# xcvr.net
KiCad netlist of a schematic drawn in Altium Designer
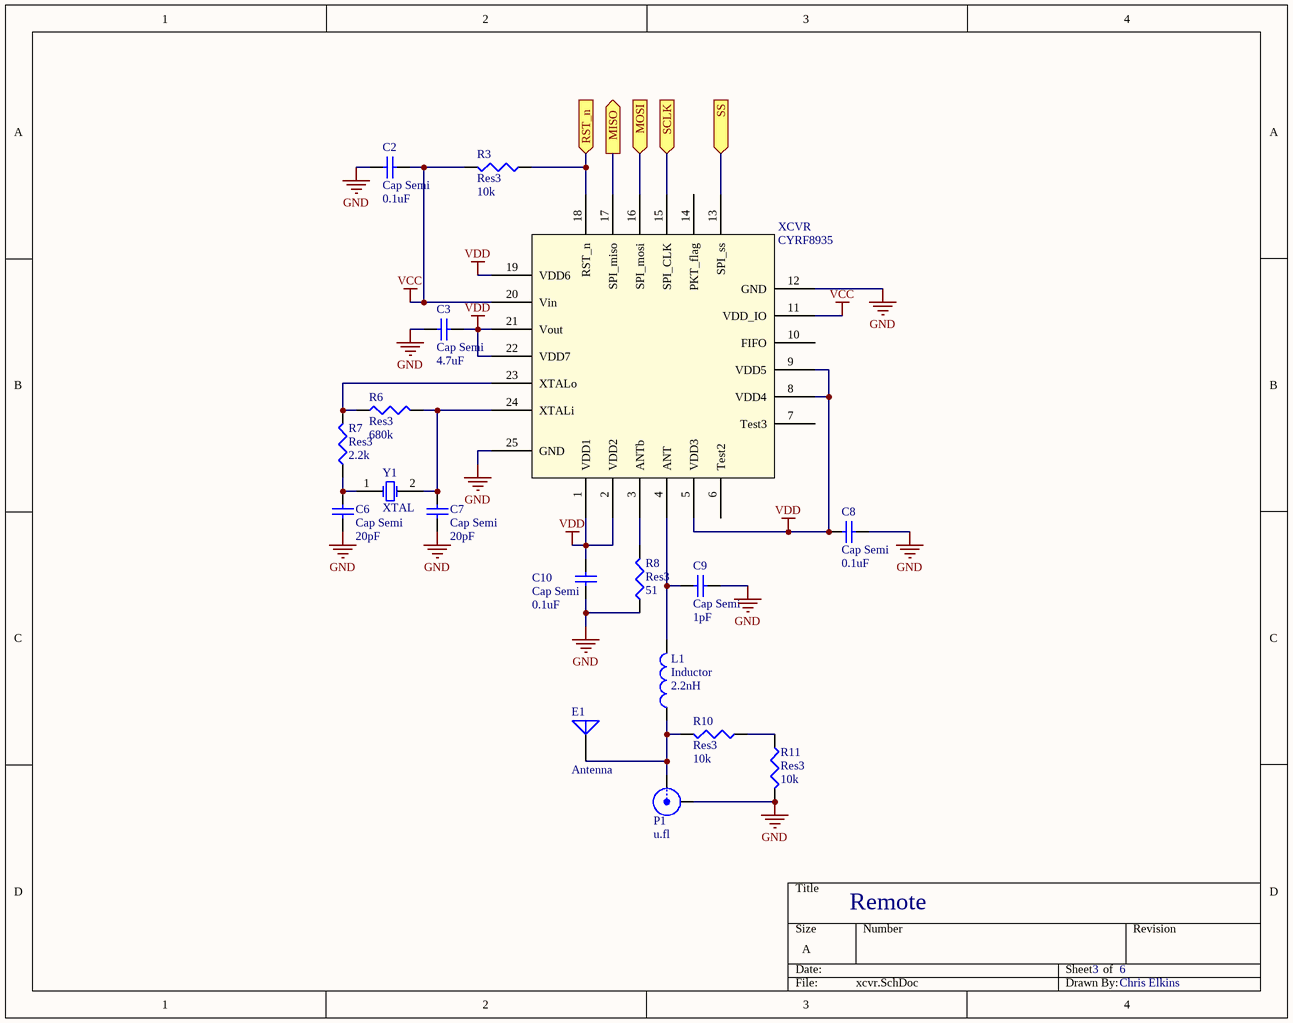
[diagram p0: xcvr.SchDoc]

(export (version "E")
  (design (tool "Eeschema 10.0.6"))
  (components
    (comp (ref "C2")
      (value "Cap Semi")
      (footprint "CAPC1608L")
      (description "Capacitor (Semiconductor SIM Model)")
      (fields (field (name "ALTIUM_VALUE") "0.1uF") (field (name "PUBLISHER") "Altium Limited"))
      (libsource (lib "Miscellaneous Devices") (part "Cap Semi"))
    )
    (comp (ref "C3")
      (value "Cap Semi")
      (footprint "CAPC1608L")
      (description "Capacitor (Semiconductor SIM Model)")
      (fields (field (name "ALTIUM_VALUE") "4.7uF") (field (name "PUBLISHER") "Altium Limited"))
      (libsource (lib "Miscellaneous Devices") (part "Cap Semi"))
    )
    (comp (ref "C6")
      (value "Cap Semi")
      (footprint "CAPC1608L")
      (description "Capacitor (Semiconductor SIM Model)")
      (fields (field (name "ALTIUM_VALUE") "20pF") (field (name "PUBLISHER") "Altium Limited"))
      (libsource (lib "Miscellaneous Devices") (part "Cap Semi"))
    )
    (comp (ref "C7")
      (value "Cap Semi")
      (footprint "CAPC1608L")
      (description "Capacitor (Semiconductor SIM Model)")
      (fields (field (name "ALTIUM_VALUE") "20pF") (field (name "PUBLISHER") "Altium Limited"))
      (libsource (lib "Miscellaneous Devices") (part "Cap Semi"))
    )
    (comp (ref "C8")
      (value "Cap Semi")
      (footprint "CAPC1608L")
      (description "Capacitor (Semiconductor SIM Model)")
      (fields (field (name "ALTIUM_VALUE") "0.1uF") (field (name "PUBLISHER") "Altium Limited"))
      (libsource (lib "Miscellaneous Devices") (part "Cap Semi"))
    )
    (comp (ref "C9")
      (value "Cap Semi")
      (footprint "CAPC1608L")
      (description "Capacitor (Semiconductor SIM Model)")
      (fields (field (name "ALTIUM_VALUE") "1pF") (field (name "PUBLISHER") "Altium Limited"))
      (libsource (lib "Miscellaneous Devices") (part "Cap Semi"))
    )
    (comp (ref "C10")
      (value "Cap Semi")
      (footprint "CAPC1608L")
      (description "Capacitor (Semiconductor SIM Model)")
      (fields (field (name "ALTIUM_VALUE") "0.1uF") (field (name "PUBLISHER") "Altium Limited"))
      (libsource (lib "Miscellaneous Devices") (part "Cap Semi"))
    )
    (comp (ref "E1")
      (value "Antenna")
      (footprint "PIN1")
      (description "Generic Antenna")
      (fields (field (name "PUBLISHER") "Altium Limited"))
      (libsource (lib "Miscellaneous Devices") (part "Antenna"))
    )
    (comp (ref "L1")
      (value "Inductor")
      (footprint "INDC1608L")
      (fields (field (name "ALTIUM_VALUE") "2.2nH") (field (name "PUBLISHER") "Altium Limited"))
      (libsource (lib "Miscellaneous Devices") (part "Inductor"))
    )
    (comp (ref "P1")
      (value "u.fl")
      (footprint "U.FL connector")
      (description "BNC Elbow Connector")
      (fields (field (name "PUBLISHER") "Altium Limited"))
      (libsource (lib "Miscellaneous Connectors") (part "BNC"))
    )
    (comp (ref "R3")
      (value "Res3")
      (footprint "RESC1608L")
      (description "Resistor")
      (fields (field (name "ALTIUM_VALUE") "10k") (field (name "PUBLISHER") "Altium Limited"))
      (libsource (lib "Miscellaneous Devices") (part "Res3"))
    )
    (comp (ref "R6")
      (value "Res3")
      (footprint "RESC1608L")
      (description "Resistor")
      (fields (field (name "ALTIUM_VALUE") "680k") (field (name "PUBLISHER") "Altium Limited"))
      (libsource (lib "Miscellaneous Devices") (part "Res3"))
    )
    (comp (ref "R7")
      (value "Res3")
      (footprint "RESC1608L")
      (description "Resistor")
      (fields (field (name "ALTIUM_VALUE") "2.2k") (field (name "PUBLISHER") "Altium Limited"))
      (libsource (lib "Miscellaneous Devices") (part "Res3"))
    )
    (comp (ref "R8")
      (value "Res3")
      (footprint "RESC1608L")
      (description "Resistor")
      (fields (field (name "ALTIUM_VALUE") "51") (field (name "PUBLISHER") "Altium Limited"))
      (libsource (lib "Miscellaneous Devices") (part "Res3"))
    )
    (comp (ref "R10")
      (value "Res3")
      (footprint "RESC1608L")
      (description "Resistor")
      (fields (field (name "ALTIUM_VALUE") "10k") (field (name "PUBLISHER") "Altium Limited"))
      (libsource (lib "Miscellaneous Devices") (part "Res3"))
    )
    (comp (ref "R11")
      (value "Res3")
      (footprint "RESC1608L")
      (description "Resistor")
      (fields (field (name "ALTIUM_VALUE") "10k") (field (name "PUBLISHER") "Altium Limited"))
      (libsource (lib "Miscellaneous Devices") (part "Res3"))
    )
    (comp (ref "XCVR")
      (value "CYRF8935")
      (footprint "QFN50P400X400-24VAL")
      (libsource (lib "Integrated_Library1") (part "CYRF8935"))
    )
    (comp (ref "Y1")
      (value "XTAL")
      (footprint "PCBComponent_1")
      (description "Crystal Oscillator")
      (fields (field (name "PUBLISHER") "Altium Limited"))
      (libsource (lib "Miscellaneous Devices") (part "XTAL"))
    )
  )
  (nets
    (net (code "1") (name "/MISO") (class "Default")
      (node (ref "XCVR") (pin "17") (pinfunction "SPI_miso_17") (pintype "passive"))
    )
    (net (code "2") (name "/MOSI") (class "Default")
      (node (ref "XCVR") (pin "16") (pinfunction "SPI_mosi_16") (pintype "passive"))
    )
    (net (code "3") (name "/RST_n") (class "Default")
      (node (ref "R3") (pin "1") (pinfunction "1_1") (pintype "passive"))
      (node (ref "XCVR") (pin "18") (pinfunction "RST_n_18") (pintype "passive"))
    )
    (net (code "4") (name "/SCLK") (class "Default")
      (node (ref "XCVR") (pin "15") (pinfunction "SPI_CLK_15") (pintype "passive"))
    )
    (net (code "5") (name "/SS") (class "Default")
      (node (ref "XCVR") (pin "13") (pinfunction "SPI_ss_13") (pintype "passive"))
    )
    (net (code "6") (name "GND") (class "Default")
      (node (ref "C10") (pin "2") (pinfunction "2_2") (pintype "passive"))
      (node (ref "C2") (pin "1") (pinfunction "1_1") (pintype "passive"))
      (node (ref "C3") (pin "1") (pinfunction "1_1") (pintype "passive"))
      (node (ref "C6") (pin "1") (pinfunction "1_1") (pintype "passive"))
      (node (ref "C7") (pin "1") (pinfunction "1_1") (pintype "passive"))
      (node (ref "C8") (pin "1") (pinfunction "1_1") (pintype "passive"))
      (node (ref "C9") (pin "2") (pinfunction "2_2") (pintype "passive"))
      (node (ref "P1") (pin "2") (pinfunction "Y_2") (pintype "passive"))
      (node (ref "R11") (pin "2") (pinfunction "2_2") (pintype "passive"))
      (node (ref "R8") (pin "1") (pinfunction "1_1") (pintype "passive"))
      (node (ref "XCVR") (pin "12") (pinfunction "GND_12") (pintype "passive"))
      (node (ref "XCVR") (pin "25") (pinfunction "GND_25") (pintype "passive"))
    )
    (net (code "7") (name "Net-(E1-A)") (class "Default")
      (node (ref "E1") (pin "1") (pinfunction "A_1") (pintype "passive"))
      (node (ref "L1") (pin "1") (pinfunction "1_1") (pintype "passive"))
      (node (ref "P1") (pin "1") (pinfunction "X_1") (pintype "passive"))
      (node (ref "R10") (pin "2") (pinfunction "2_2") (pintype "passive"))
    )
    (net (code "8") (name "Net-(R10-Pad1)") (class "Default")
      (node (ref "R10") (pin "1") (pinfunction "1_1") (pintype "passive"))
      (node (ref "R11") (pin "1") (pinfunction "1_1") (pintype "passive"))
    )
    (net (code "9") (name "Net-(XCVR-ANT)") (class "Default")
      (node (ref "C9") (pin "1") (pinfunction "1_1") (pintype "passive"))
      (node (ref "L1") (pin "2") (pinfunction "2_2") (pintype "passive"))
      (node (ref "XCVR") (pin "4") (pinfunction "ANT_4") (pintype "passive"))
    )
    (net (code "10") (name "Net-(XCVR-ANTb)") (class "Default")
      (node (ref "R8") (pin "2") (pinfunction "2_2") (pintype "passive"))
      (node (ref "XCVR") (pin "3") (pinfunction "ANTb_3") (pintype "passive"))
    )
    (net (code "11") (name "Net-(XCVR-XTALi)") (class "Default")
      (node (ref "C7") (pin "2") (pinfunction "2_2") (pintype "passive"))
      (node (ref "R6") (pin "2") (pinfunction "2_2") (pintype "passive"))
      (node (ref "XCVR") (pin "24") (pinfunction "XTALi_24") (pintype "passive"))
      (node (ref "Y1") (pin "2") (pinfunction "OSC2_2") (pintype "passive"))
    )
    (net (code "12") (name "Net-(XCVR-XTALo)") (class "Default")
      (node (ref "R6") (pin "1") (pinfunction "1_1") (pintype "passive"))
      (node (ref "R7") (pin "2") (pinfunction "2_2") (pintype "passive"))
      (node (ref "XCVR") (pin "23") (pinfunction "XTALo_23") (pintype "passive"))
    )
    (net (code "13") (name "Net-(Y1-OSC1)") (class "Default")
      (node (ref "C6") (pin "2") (pinfunction "2_2") (pintype "passive"))
      (node (ref "R7") (pin "1") (pinfunction "1_1") (pintype "passive"))
      (node (ref "Y1") (pin "1") (pinfunction "OSC1_1") (pintype "passive"))
    )
    (net (code "14") (name "VCC") (class "Default")
      (node (ref "C2") (pin "2") (pinfunction "2_2") (pintype "passive"))
      (node (ref "R3") (pin "2") (pinfunction "2_2") (pintype "passive"))
      (node (ref "XCVR") (pin "11") (pinfunction "VDD_IO_11") (pintype "passive"))
      (node (ref "XCVR") (pin "20") (pinfunction "Vin_20") (pintype "passive"))
    )
    (net (code "15") (name "VDD") (class "Default")
      (node (ref "C10") (pin "1") (pinfunction "1_1") (pintype "passive"))
      (node (ref "C3") (pin "2") (pinfunction "2_2") (pintype "passive"))
      (node (ref "C8") (pin "2") (pinfunction "2_2") (pintype "passive"))
      (node (ref "XCVR") (pin "1") (pinfunction "VDD1_1") (pintype "passive"))
      (node (ref "XCVR") (pin "19") (pinfunction "VDD6_19") (pintype "passive"))
      (node (ref "XCVR") (pin "2") (pinfunction "VDD2_2") (pintype "passive"))
      (node (ref "XCVR") (pin "21") (pinfunction "Vout_21") (pintype "passive"))
      (node (ref "XCVR") (pin "22") (pinfunction "VDD7_22") (pintype "passive"))
      (node (ref "XCVR") (pin "5") (pinfunction "VDD3_5") (pintype "passive"))
      (node (ref "XCVR") (pin "8") (pinfunction "VDD4_8") (pintype "passive"))
      (node (ref "XCVR") (pin "9") (pinfunction "VDD5_9") (pintype "passive"))
    )
    (net (code "16") (name "unconnected-(XCVR-FIFO-Pad10)") (class "Default")
      (node (ref "XCVR") (pin "10") (pinfunction "FIFO_10") (pintype "passive"))
    )
    (net (code "17") (name "unconnected-(XCVR-PKT_flag-Pad14)") (class "Default")
      (node (ref "XCVR") (pin "14") (pinfunction "PKT_flag_14") (pintype "passive"))
    )
    (net (code "18") (name "unconnected-(XCVR-Test2-Pad6)") (class "Default")
      (node (ref "XCVR") (pin "6") (pinfunction "Test2_6") (pintype "passive"))
    )
    (net (code "19") (name "unconnected-(XCVR-Test3-Pad7)") (class "Default")
      (node (ref "XCVR") (pin "7") (pinfunction "Test3_7") (pintype "passive"))
    )
  )
)
